# POWER.net
KiCad netlist of a schematic drawn in Altium Designer
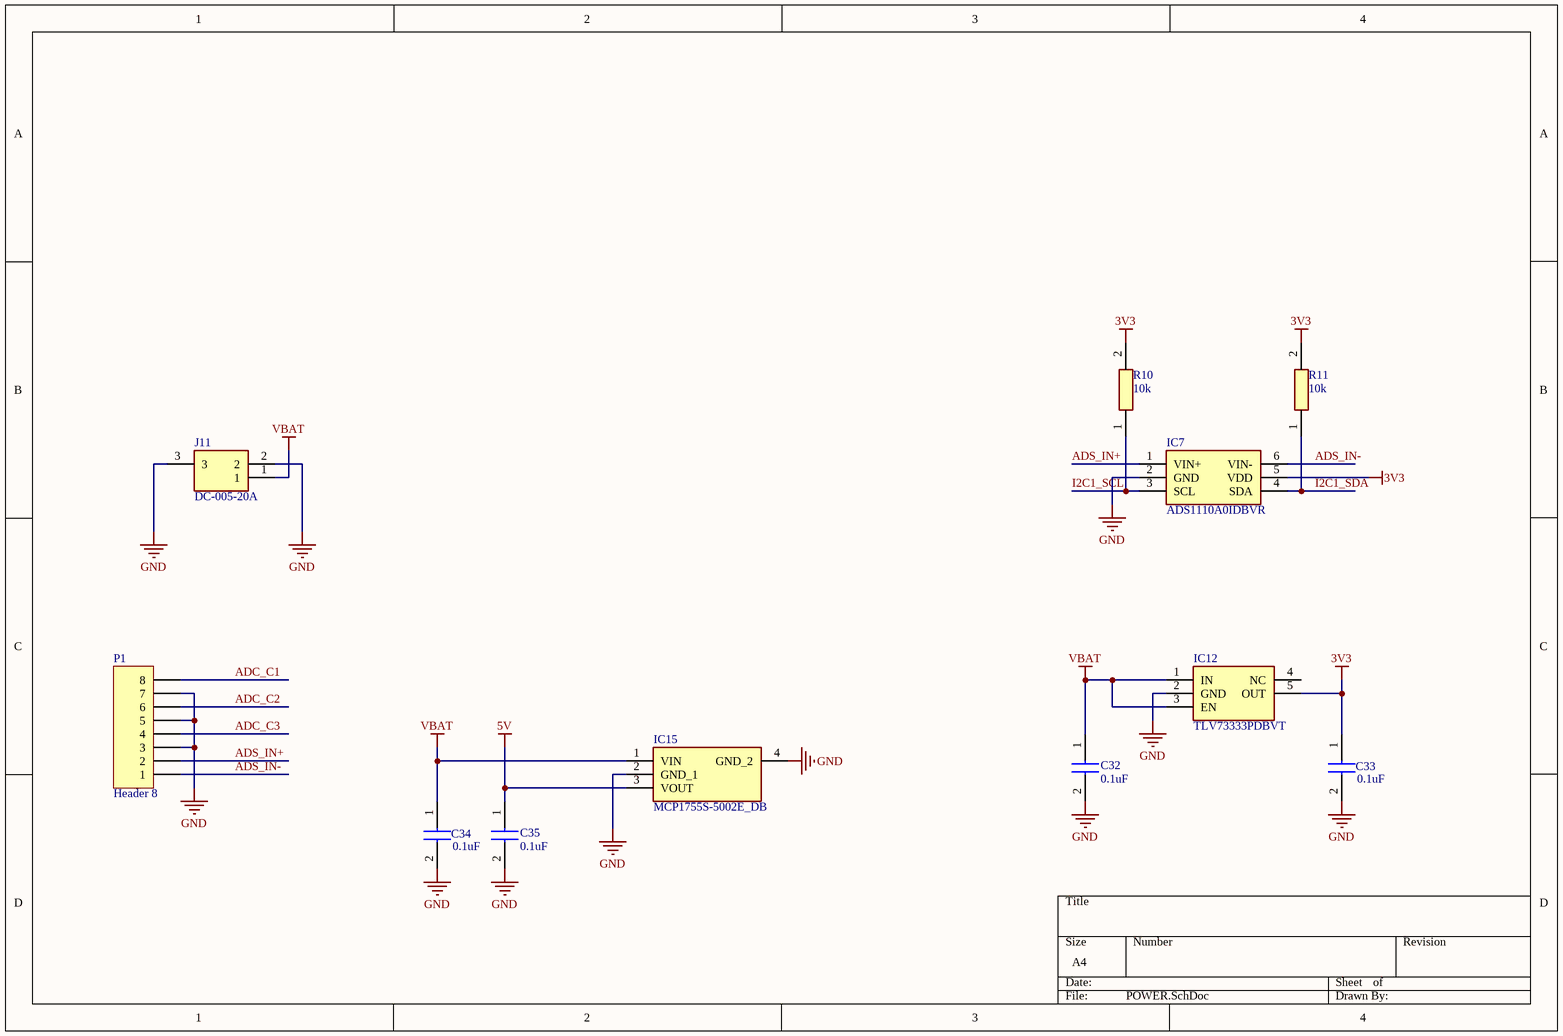
[diagram p0: POWER.SchDoc]

(export (version "E")
  (design (tool "Eeschema 10.0.6"))
  (components
    (comp (ref "C32")
      (value "0.1uF")
      (footprint "SamacSys:CAPC2012X94N")
      (description "Capacitor")
      (fields
        (field (name "MANUFACTURER_PART_NUMBER") "08055A130JAT2A")
        (field (name "MOUSER PART NUMBER") "581-08055A130JAT2A")
      )
      (libsource (lib "SamacSys") (part "08055A130JAT2A"))
    )
    (comp (ref "C33")
      (value "0.1uF")
      (footprint "SamacSys:CAPC2012X94N")
      (description "Capacitor")
      (fields
        (field (name "MANUFACTURER_PART_NUMBER") "08055A130JAT2A")
        (field (name "MOUSER PART NUMBER") "581-08055A130JAT2A")
      )
      (libsource (lib "SamacSys") (part "08055A130JAT2A"))
    )
    (comp (ref "C34")
      (value "0.1uF")
      (footprint "SamacSys:CAPC2012X94N")
      (description "Capacitor")
      (fields
        (field (name "MANUFACTURER_PART_NUMBER") "08055A130JAT2A")
        (field (name "MOUSER PART NUMBER") "581-08055A130JAT2A")
      )
      (libsource (lib "SamacSys") (part "08055A130JAT2A"))
    )
    (comp (ref "C35")
      (value "0.1uF")
      (footprint "SamacSys:CAPC2012X94N")
      (description "Capacitor")
      (fields
        (field (name "MANUFACTURER_PART_NUMBER") "08055A130JAT2A")
        (field (name "MOUSER PART NUMBER") "581-08055A130JAT2A")
      )
      (libsource (lib "SamacSys") (part "08055A130JAT2A"))
    )
    (comp (ref "IC7")
      (value "ADS1110A0IDBVR")
      (footprint "SamacSys:SOT95P280X145-6N")
      (description "Integrated Circuit")
      (fields (field (name "MOUSER PART NUMBER") "595-ADS1110A0IDBVR"))
      (libsource (lib "*") (part "ADS1110A0IDBVR"))
    )
    (comp (ref "IC12")
      (value "TLV73333PDBVT")
      (footprint "SamacSys:SOT95P280X145-5N")
      (description "Integrated Circuit")
      (fields (field (name "MOUSER PART NUMBER") "595-TLV73333PDBVT"))
      (libsource (lib "*") (part "TLV73333PDBVT"))
    )
    (comp (ref "IC15")
      (value "MCP1755S-5002E_DB")
      (footprint "SamacSys:SOT230P700X180-4N")
      (description "Integrated Circuit")
      (fields
        (field (name "MANUFACTURER_PART_NUMBER") "MCP1755S-5002E/DB")
        (field (name "MOUSER PART NUMBER") "579-MCP1755S-5002EDB")
      )
      (libsource (lib "*") (part "MCP1755S-5002E_DB"))
    )
    (comp (ref "J11")
      (value "DC-005-20A")
      (footprint "SamacSys:DC00520A")
      (description "Connector")
      (libsource (lib "*") (part "DC-005-20A"))
    )
    (comp (ref "P1")
      (value "Header 8")
      (footprint "HDR1X8")
      (description "Header, 8-Pin")
      (fields (field (name "PUBLISHER") "Altium Limited"))
      (libsource (lib "Miscellaneous Connectors") (part "Header 8"))
    )
    (comp (ref "R10")
      (value "10k")
      (footprint "SamacSys:RESC2012X65N")
      (description "Resistor")
      (fields (field (name "MANUFACTURER_PART_NUMBER") "CPF0805B102RE1"))
      (libsource (lib "SamacSys") (part "CPF0805B102RE1"))
    )
    (comp (ref "R11")
      (value "10k")
      (footprint "SamacSys:RESC2012X65N")
      (description "Resistor")
      (fields (field (name "MANUFACTURER_PART_NUMBER") "CPF0805B102RE1"))
      (libsource (lib "SamacSys") (part "CPF0805B102RE1"))
    )
  )
  (nets
    (net (code "1") (name "/ADC_C1") (class "Default")
      (node (ref "P1") (pin "8") (pinfunction "8_8") (pintype "passive"))
    )
    (net (code "2") (name "/ADC_C2") (class "Default")
      (node (ref "P1") (pin "6") (pinfunction "6_6") (pintype "passive"))
    )
    (net (code "3") (name "/ADC_C3") (class "Default")
      (node (ref "P1") (pin "4") (pinfunction "4_4") (pintype "passive"))
    )
    (net (code "4") (name "/ADS_IN+") (class "Default")
      (node (ref "IC7") (pin "1") (pinfunction "VIN+_1") (pintype "passive"))
      (node (ref "P1") (pin "2") (pinfunction "2_2") (pintype "passive"))
    )
    (net (code "5") (name "/ADS_IN-") (class "Default")
      (node (ref "IC7") (pin "6") (pinfunction "VIN-_6") (pintype "passive"))
      (node (ref "P1") (pin "1") (pinfunction "1_1") (pintype "passive"))
    )
    (net (code "6") (name "/I2C1_SCL") (class "Default")
      (node (ref "IC7") (pin "3") (pinfunction "SCL_3") (pintype "passive"))
      (node (ref "R10") (pin "1") (pinfunction "1_1") (pintype "passive"))
    )
    (net (code "7") (name "/I2C1_SDA") (class "Default")
      (node (ref "IC7") (pin "4") (pinfunction "SDA_4") (pintype "passive"))
      (node (ref "R11") (pin "1") (pinfunction "1_1") (pintype "passive"))
    )
    (net (code "8") (name "3V3") (class "Default")
      (node (ref "C33") (pin "1") (pinfunction "1_1") (pintype "passive"))
      (node (ref "IC12") (pin "5") (pinfunction "OUT_5") (pintype "passive"))
      (node (ref "IC7") (pin "5") (pinfunction "VDD_5") (pintype "passive"))
      (node (ref "R10") (pin "2") (pinfunction "2_2") (pintype "passive"))
      (node (ref "R11") (pin "2") (pinfunction "2_2") (pintype "passive"))
    )
    (net (code "9") (name "5V") (class "Default")
      (node (ref "C35") (pin "1") (pinfunction "1_1") (pintype "passive"))
      (node (ref "IC15") (pin "3") (pinfunction "VOUT_3") (pintype "passive"))
    )
    (net (code "10") (name "GND") (class "Default")
      (node (ref "C32") (pin "2") (pinfunction "2_2") (pintype "passive"))
      (node (ref "C33") (pin "2") (pinfunction "2_2") (pintype "passive"))
      (node (ref "C34") (pin "2") (pinfunction "2_2") (pintype "passive"))
      (node (ref "C35") (pin "2") (pinfunction "2_2") (pintype "passive"))
      (node (ref "IC12") (pin "2") (pinfunction "GND_2") (pintype "passive"))
      (node (ref "IC15") (pin "2") (pinfunction "GND_1_2") (pintype "passive"))
      (node (ref "IC15") (pin "4") (pinfunction "GND_2_4") (pintype "passive"))
      (node (ref "IC7") (pin "2") (pinfunction "GND_2") (pintype "passive"))
      (node (ref "J11") (pin "2") (pinfunction "2_2") (pintype "passive"))
      (node (ref "J11") (pin "3") (pinfunction "3_3") (pintype "passive"))
      (node (ref "P1") (pin "3") (pinfunction "3_3") (pintype "passive"))
      (node (ref "P1") (pin "5") (pinfunction "5_5") (pintype "passive"))
      (node (ref "P1") (pin "7") (pinfunction "7_7") (pintype "passive"))
    )
    (net (code "11") (name "VBAT") (class "Default")
      (node (ref "C32") (pin "1") (pinfunction "1_1") (pintype "passive"))
      (node (ref "C34") (pin "1") (pinfunction "1_1") (pintype "passive"))
      (node (ref "IC12") (pin "1") (pinfunction "IN_1") (pintype "passive"))
      (node (ref "IC12") (pin "3") (pinfunction "EN_3") (pintype "passive"))
      (node (ref "IC15") (pin "1") (pinfunction "VIN_1") (pintype "passive"))
      (node (ref "J11") (pin "1") (pinfunction "1_1") (pintype "passive"))
    )
    (net (code "12") (name "unconnected-(IC12-NC-Pad4)") (class "Default")
      (node (ref "IC12") (pin "4") (pinfunction "NC_4") (pintype "passive"))
    )
  )
)
